# 5V_Efuses.net
KiCad netlist of a schematic drawn in Altium Designer
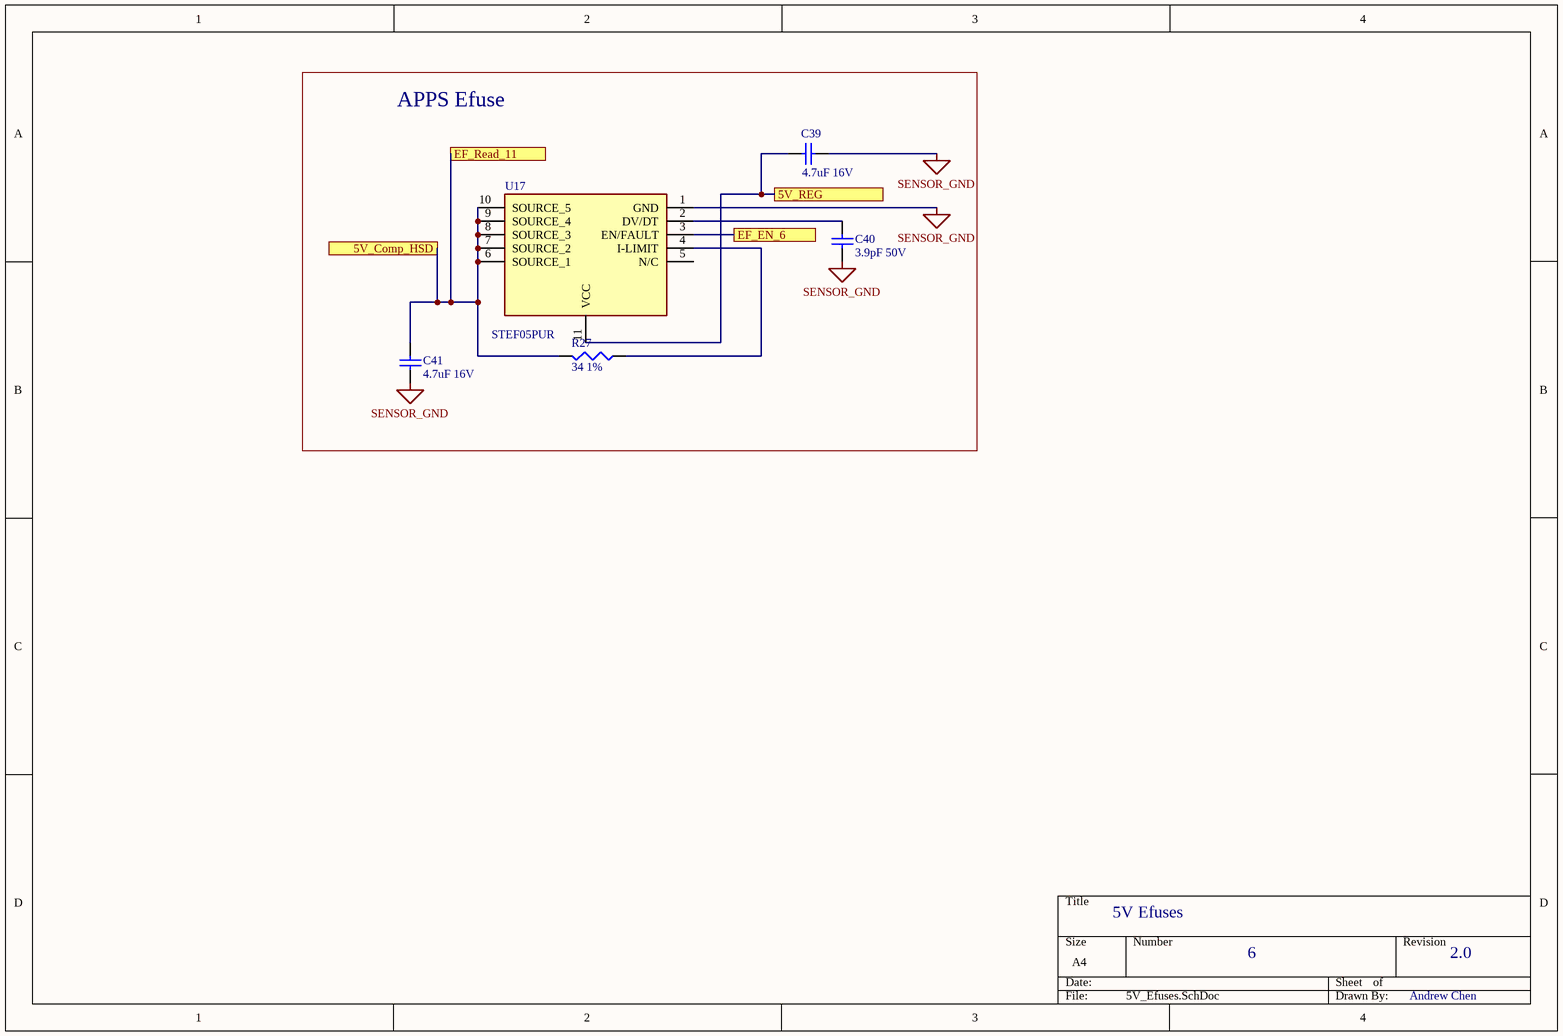
[diagram p0: 5V_Efuses.SchDoc]

(export (version "E")
  (design (tool "Eeschema 10.0.6"))
  (components
    (comp (ref "C39")
      (value "4.7uF 16V")
      (footprint "C1206")
      (description "Capacitor (Semiconductor SIM Model)")
      (fields (field (name "PUBLISHER") "Altium Limited"))
      (libsource (lib "Miscellaneous Devices") (part "Cap Semi"))
    )
    (comp (ref "C40")
      (value "3.9pF 50V")
      (footprint "C1206")
      (description "Capacitor (Semiconductor SIM Model)")
      (fields (field (name "PUBLISHER") "Altium Limited"))
      (libsource (lib "Miscellaneous Devices") (part "Cap Semi"))
    )
    (comp (ref "C41")
      (value "4.7uF 16V")
      (footprint "C1206")
      (description "Capacitor (Semiconductor SIM Model)")
      (fields (field (name "PUBLISHER") "Altium Limited"))
      (libsource (lib "Miscellaneous Devices") (part "Cap Semi"))
    )
    (comp (ref "R27")
      (value "34 1%")
      (footprint "J1-0603")
      (description "Resistor")
      (fields (field (name "PUBLISHER") "Altium Limited"))
      (libsource (lib "Miscellaneous Devices") (part "Res3"))
    )
    (comp (ref "U17")
      (value "STEF05PUR")
      (footprint "SamacSys:SON50P300X300X100-11N-D")
      (description "Integrated Circuit")
      (fields
        (field (name "MANUFACTURER_PART_NUMBER") "STEF12EPUR")
        (field (name "MOUSER PART NUMBER") "511-STEF12EPUR")
      )
      (libsource (lib "*") (part "STEF12EPUR"))
    )
  )
  (nets
    (net (code "1") (name "/5V_Comp_HSD") (class "Default")
      (node (ref "C41") (pin "1") (pinfunction "1_1") (pintype "passive"))
      (node (ref "R27") (pin "2") (pinfunction "2_2") (pintype "passive"))
      (node (ref "U17") (pin "10") (pinfunction "SOURCE_5_10") (pintype "passive"))
      (node (ref "U17") (pin "6") (pinfunction "SOURCE_1_6") (pintype "passive"))
      (node (ref "U17") (pin "7") (pinfunction "SOURCE_2_7") (pintype "passive"))
      (node (ref "U17") (pin "8") (pinfunction "SOURCE_3_8") (pintype "passive"))
      (node (ref "U17") (pin "9") (pinfunction "SOURCE_4_9") (pintype "passive"))
    )
    (net (code "2") (name "/5V_REG") (class "Default")
      (node (ref "C39") (pin "1") (pinfunction "1_1") (pintype "passive"))
      (node (ref "U17") (pin "11") (pinfunction "VCC_11") (pintype "passive"))
    )
    (net (code "4") (name "/EF_EN_6") (class "Default")
      (node (ref "U17") (pin "3") (pinfunction "EN/FAULT_3") (pintype "passive"))
    )
    (net (code "5") (name "Net-(U17-DV{slash}DT)") (class "Default")
      (node (ref "C40") (pin "1") (pinfunction "1_1") (pintype "passive"))
      (node (ref "U17") (pin "2") (pinfunction "DV/DT_2") (pintype "passive"))
    )
    (net (code "6") (name "Net-(U17-I-LIMIT)") (class "Default")
      (node (ref "R27") (pin "1") (pinfunction "1_1") (pintype "passive"))
      (node (ref "U17") (pin "4") (pinfunction "I-LIMIT_4") (pintype "passive"))
    )
    (net (code "7") (name "SENSOR_GND") (class "Default")
      (node (ref "C39") (pin "2") (pinfunction "2_2") (pintype "passive"))
      (node (ref "C40") (pin "2") (pinfunction "2_2") (pintype "passive"))
      (node (ref "C41") (pin "2") (pinfunction "2_2") (pintype "passive"))
      (node (ref "U17") (pin "1") (pinfunction "GND_1") (pintype "passive"))
    )
    (net (code "8") (name "unconnected-(U17-N{slash}C-Pad5)") (class "Default")
      (node (ref "U17") (pin "5") (pinfunction "N/C_5") (pintype "passive"))
    )
  )
)
